# quadcopter.net
KiCad netlist of a schematic drawn in EAGLE
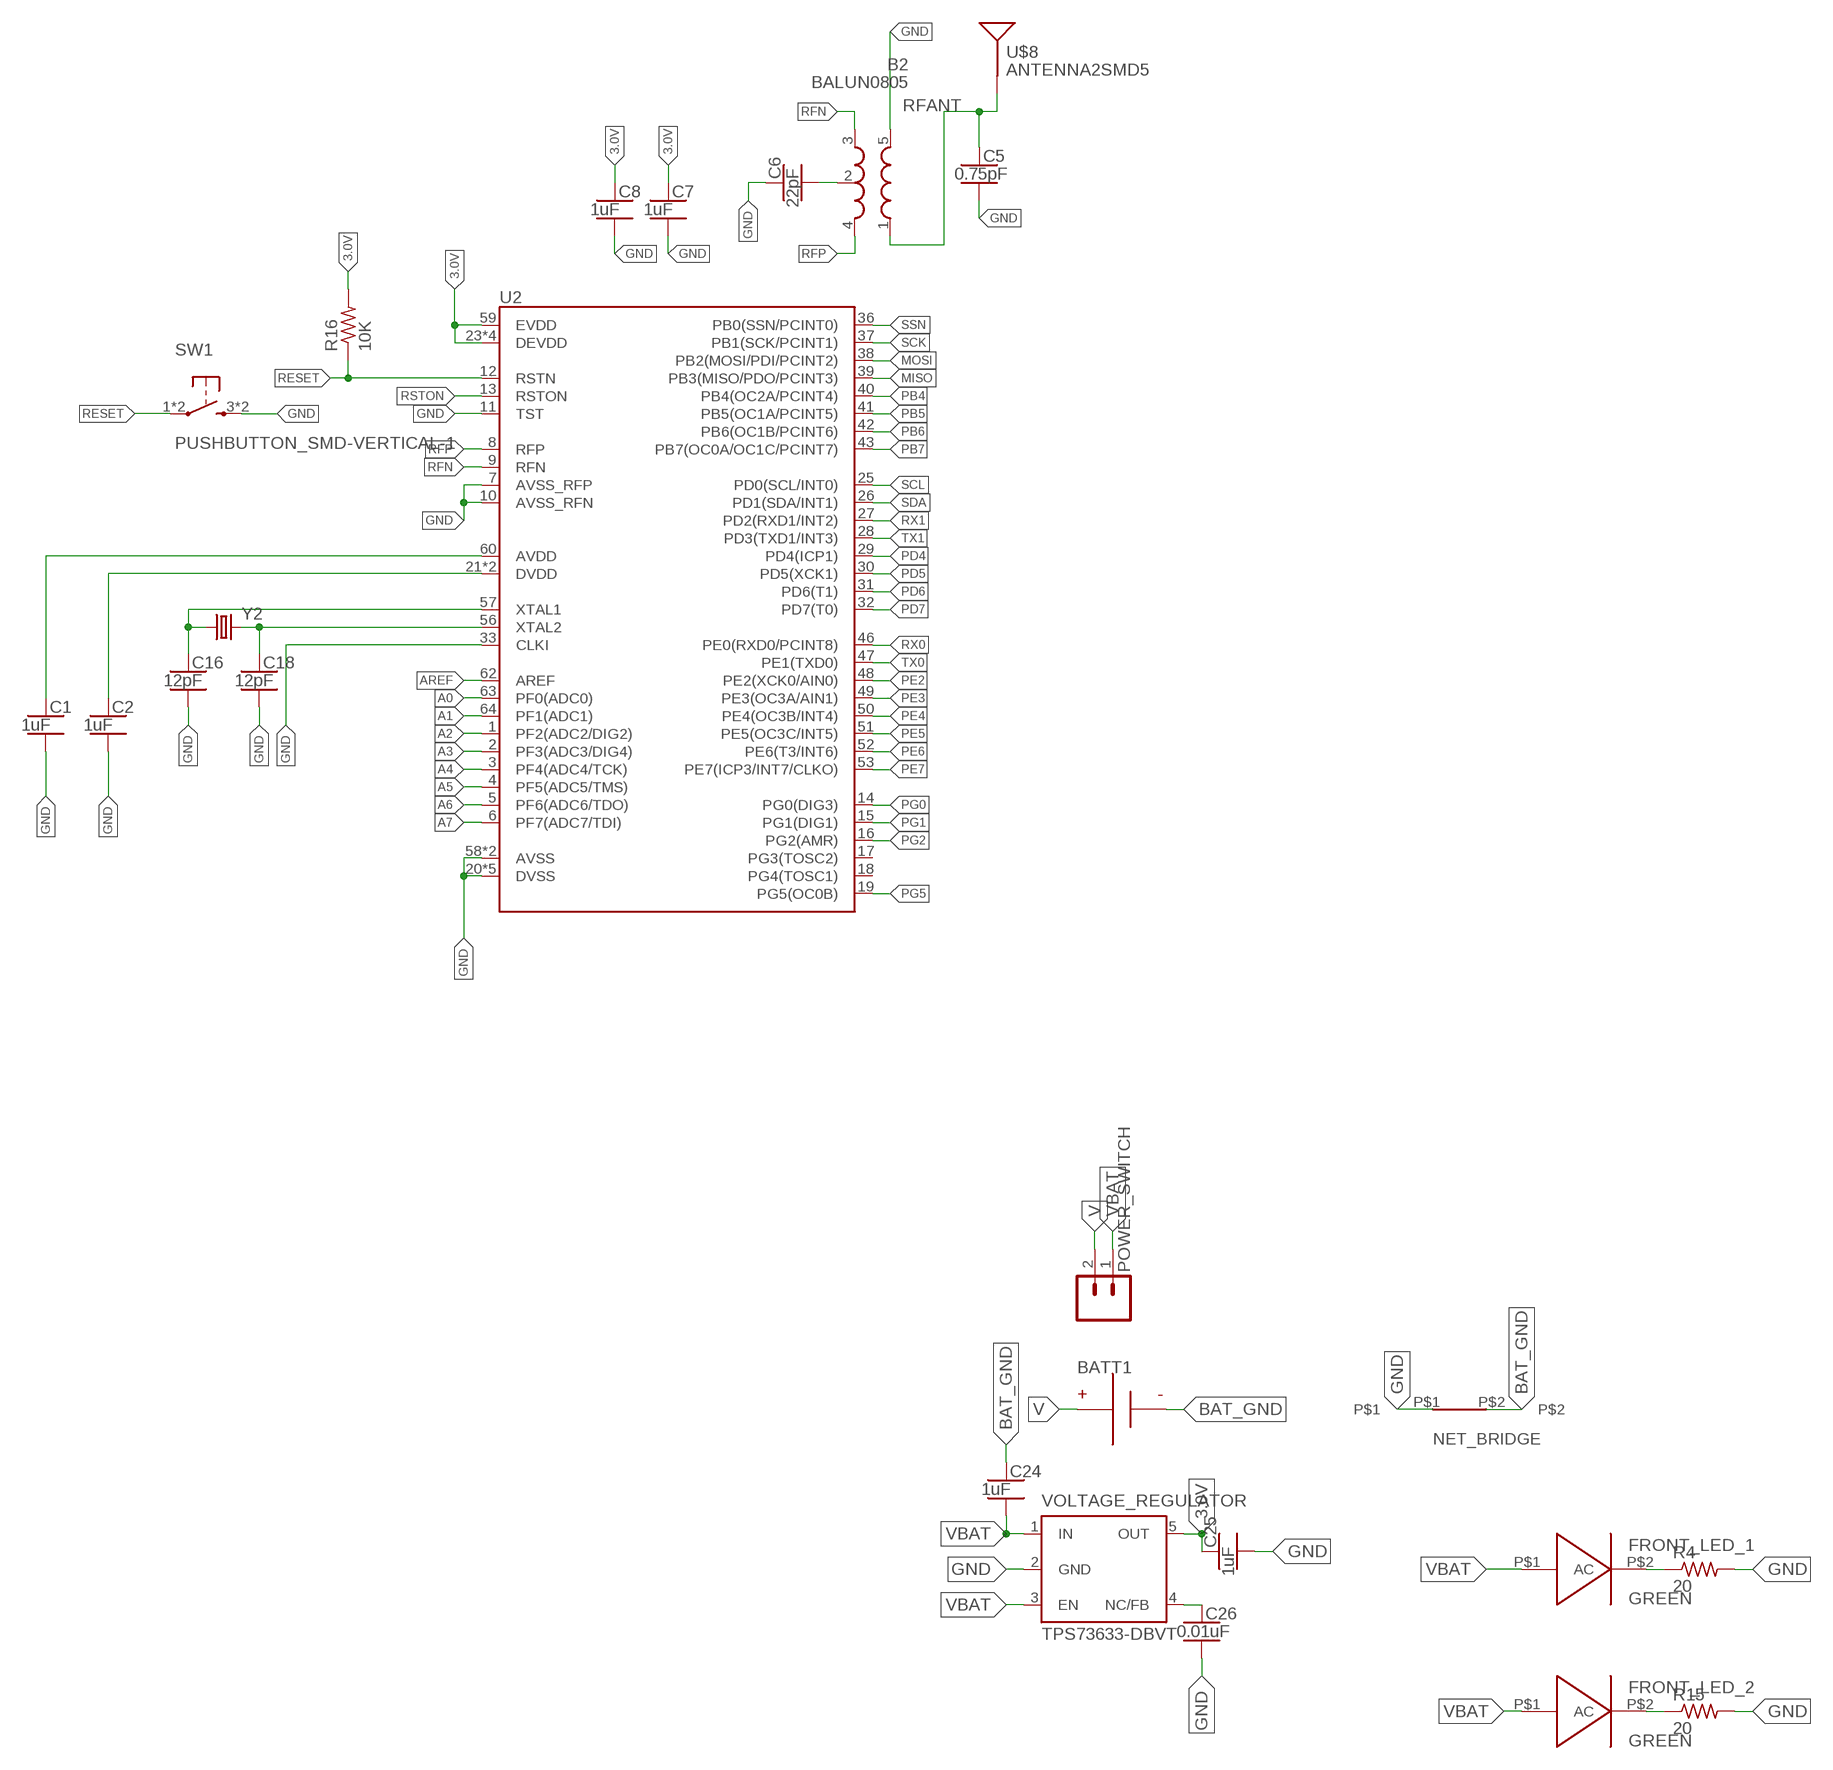
[diagram p0: schematic, sheet 1, part 1 of 2]
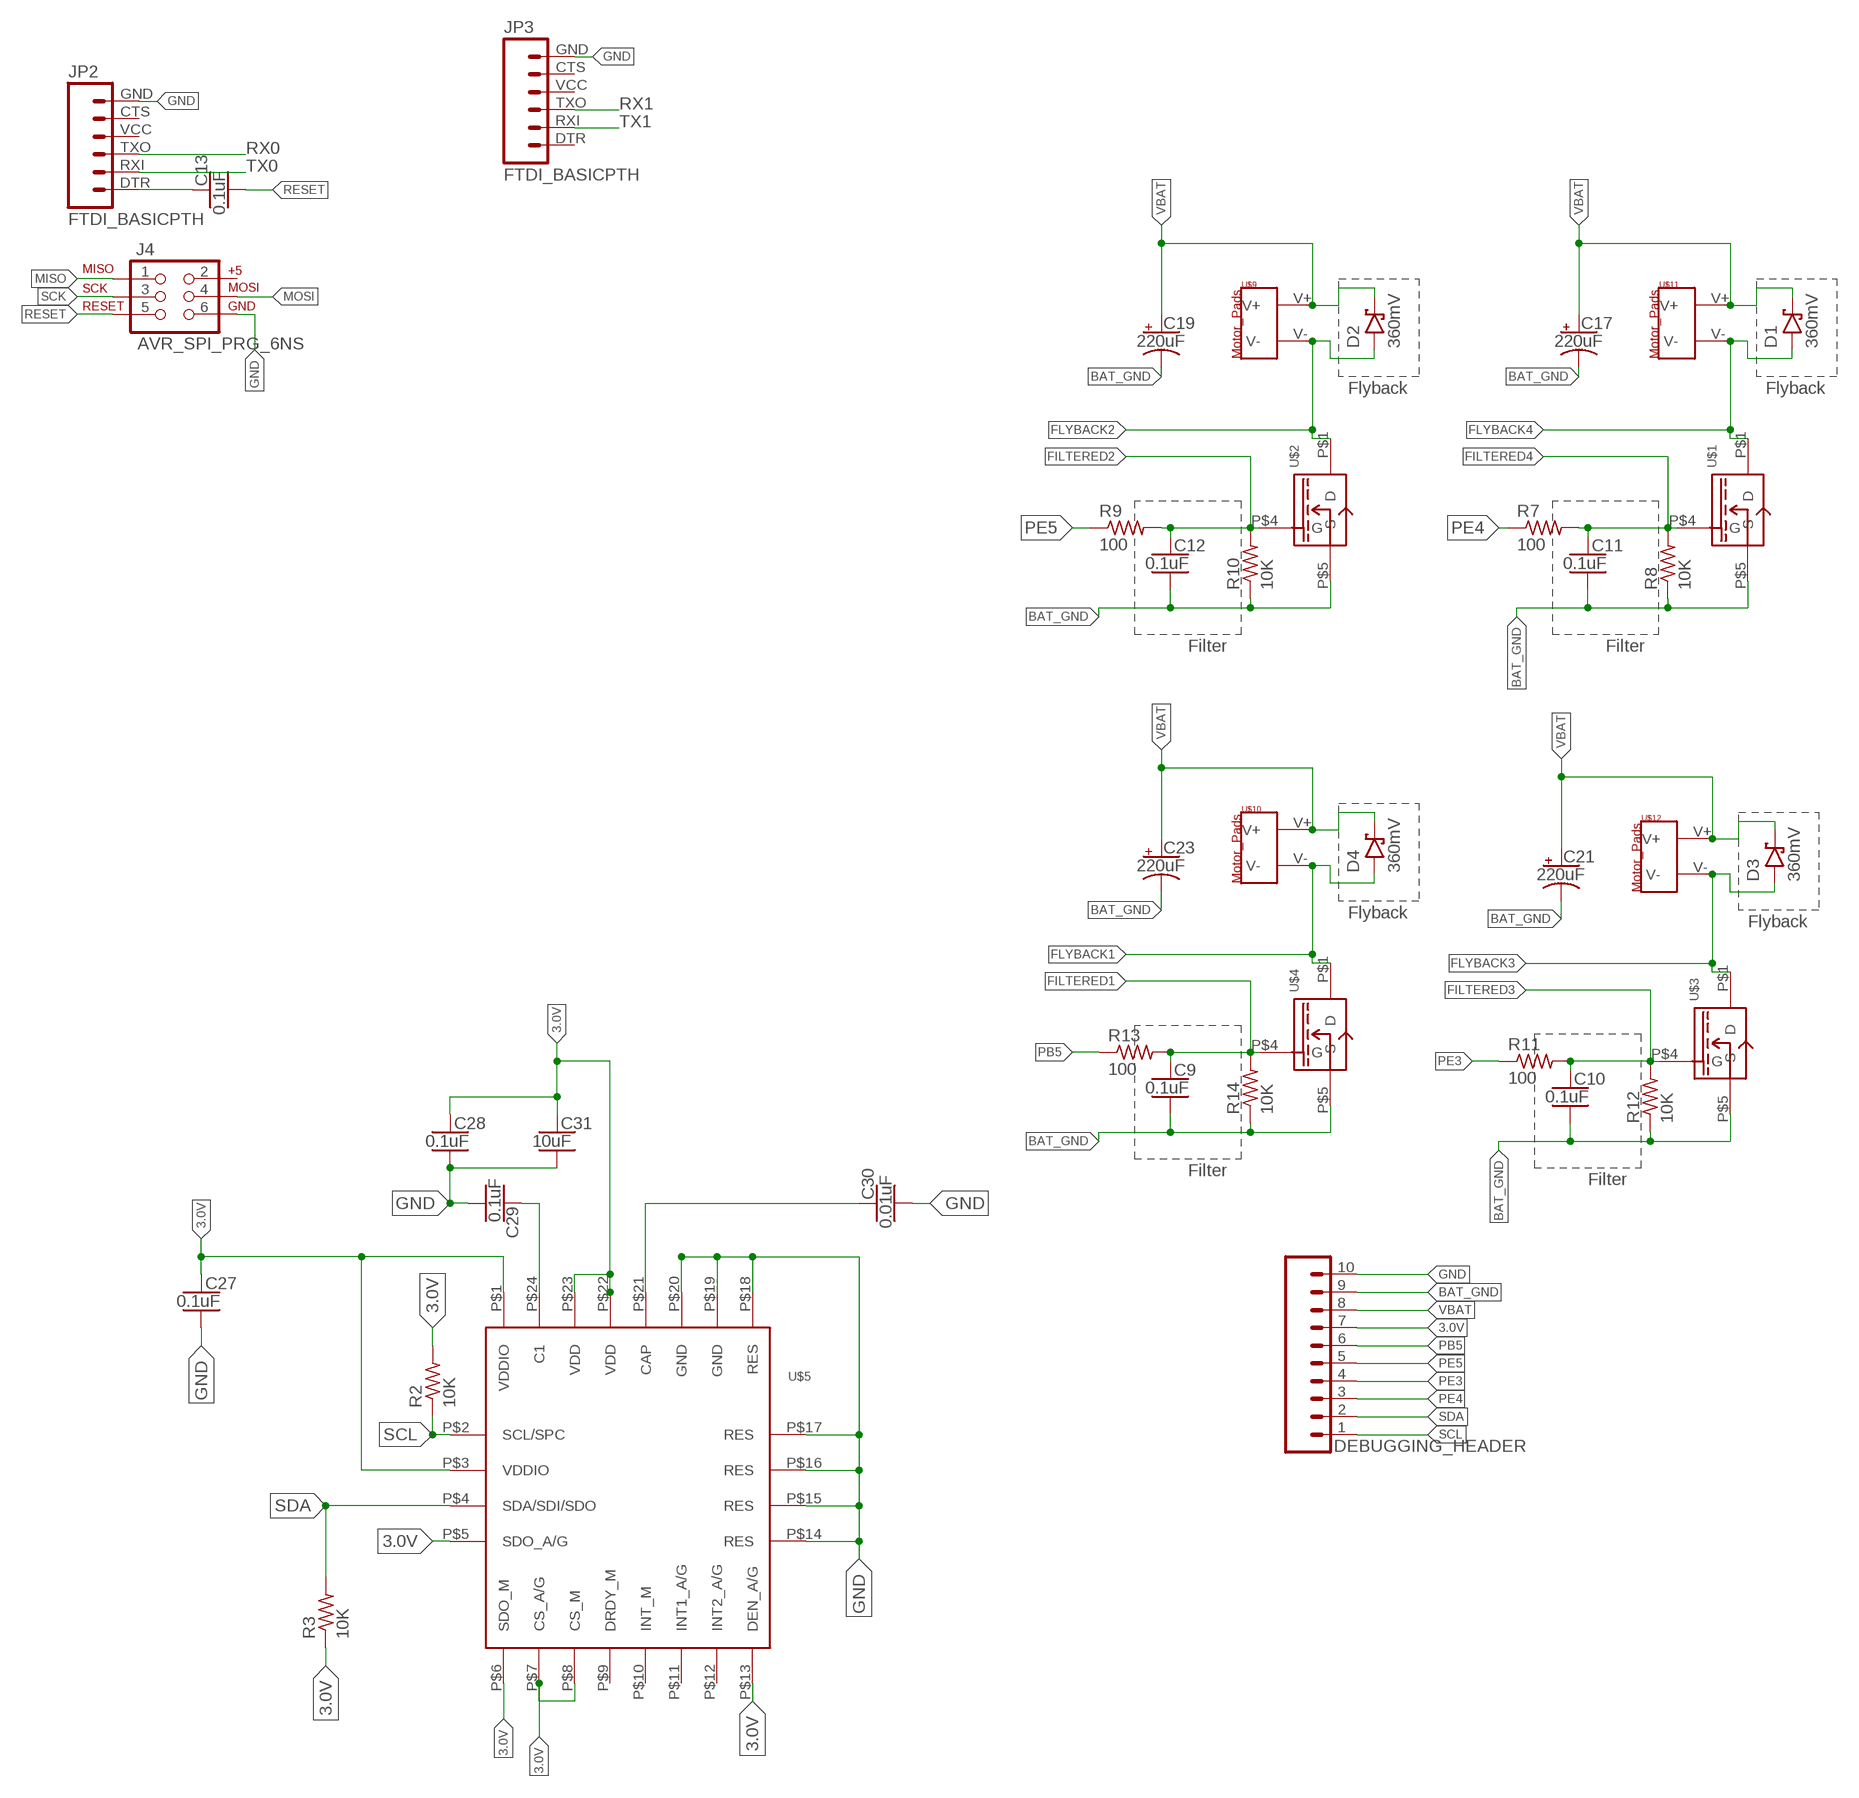
[diagram p1: schematic, sheet 1, part 2 of 2]

(export (version "E")
  (design (tool "Eeschema 10.0.6"))
  (components
    (comp (ref "B2")
      (value "BALUN0805")
      (footprint "eagle-import:BALUN")
      (fields (field (name "MFR") "Wurth Electronics Inc") (field (name "MPN") "748421245"))
      (libsource (lib "eagle-import") (part "BALUN0805"))
    )
    (comp (ref "BATT1")
      (value "BATTERY-HUBSAN-W/HOLDER")
      (footprint "eagle-import:BATTERY-W_HOLDER-380MAH-HUBSAN")
      (fields
        (field (name "MFR") "HUBSAN")
        (field (name "MPN") "X4-H107C-8-in-1")
        (field (name "CREATOR") "Swanson")
      )
      (libsource (lib "eagle-import") (part "BATTERY-HUBSAN-W/HOLDER"))
    )
    (comp (ref "C1")
      (value "1uF")
      (footprint "eagle-import:CAPC2012X140_HS")
      (fields
        (field (name "MFR") "Murata Electronics North America")
        (field (name "MPN") "GRM21BR71H105KA12L")
      )
      (libsource (lib "eagle-import") (part "CAPACITOR-NP_SMD-2012-0805_CERAMIC-1UF"))
    )
    (comp (ref "C2")
      (value "1uF")
      (footprint "eagle-import:CAPC2012X140_HS")
      (fields
        (field (name "MFR") "Murata Electronics North America")
        (field (name "MPN") "GRM21BR71H105KA12L")
      )
      (libsource (lib "eagle-import") (part "CAPACITOR-NP_SMD-2012-0805_CERAMIC-1UF"))
    )
    (comp (ref "C5")
      (value "0.75pF")
      (footprint "eagle-import:CAPC2012X140_HS")
      (fields
        (field (name "MFR") "Murata Electronics North America")
        (field (name "MPN") "GQM2195C2AR75CB01D")
      )
      (libsource (lib "eagle-import") (part "CAPACITOR-NP_SMD-2012-0805_CERAMIC-0.75PF"))
    )
    (comp (ref "C6")
      (value "22pF")
      (footprint "eagle-import:CAPC2012X140_HS")
      (fields
        (field (name "MFR") "Murata Electronics North America")
        (field (name "MPN") "GRM21A5C2E220JW01D")
      )
      (libsource (lib "eagle-import") (part "CAPACITOR-NP_SMD-2012-0805_CERAMIC-22PF"))
    )
    (comp (ref "C7")
      (value "1uF")
      (footprint "eagle-import:CAPC2012X140_HS")
      (fields
        (field (name "MFR") "Murata Electronics North America")
        (field (name "MPN") "GRM21BR71H105KA12L")
      )
      (libsource (lib "eagle-import") (part "CAPACITOR-NP_SMD-2012-0805_CERAMIC-1UF"))
    )
    (comp (ref "C8")
      (value "1uF")
      (footprint "eagle-import:CAPC2012X140_HS")
      (fields
        (field (name "MFR") "Murata Electronics North America")
        (field (name "MPN") "GRM21BR71H105KA12L")
      )
      (libsource (lib "eagle-import") (part "CAPACITOR-NP_SMD-2012-0805_CERAMIC-1UF"))
    )
    (comp (ref "C9")
      (value "0.1uF")
      (footprint "eagle-import:CAPC2012X140_HS")
      (fields
        (field (name "MFR") "Murata Electronics North America")
        (field (name "MPN") "GRM21BR71H104KA01L")
      )
      (libsource (lib "eagle-import") (part "CAPACITOR-NP_SMD-2012-0805_CERAMIC-0.1UF"))
    )
    (comp (ref "C10")
      (value "0.1uF")
      (footprint "eagle-import:CAPC2012X140_HS")
      (fields
        (field (name "MFR") "Murata Electronics North America")
        (field (name "MPN") "GRM21BR71H104KA01L")
      )
      (libsource (lib "eagle-import") (part "CAPACITOR-NP_SMD-2012-0805_CERAMIC-0.1UF"))
    )
    (comp (ref "C11")
      (value "0.1uF")
      (footprint "eagle-import:CAPC2012X140_HS")
      (fields
        (field (name "MFR") "Murata Electronics North America")
        (field (name "MPN") "GRM21BR71H104KA01L")
      )
      (libsource (lib "eagle-import") (part "CAPACITOR-NP_SMD-2012-0805_CERAMIC-0.1UF"))
    )
    (comp (ref "C12")
      (value "0.1uF")
      (footprint "eagle-import:CAPC2012X140_HS")
      (fields
        (field (name "MFR") "Murata Electronics North America")
        (field (name "MPN") "GRM21BR71H104KA01L")
      )
      (libsource (lib "eagle-import") (part "CAPACITOR-NP_SMD-2012-0805_CERAMIC-0.1UF"))
    )
    (comp (ref "C13")
      (value "0.1uF")
      (footprint "eagle-import:CAPC2012X140_HS")
      (fields
        (field (name "MFR") "Murata Electronics North America")
        (field (name "MPN") "GRM21BR71H104KA01L")
      )
      (libsource (lib "eagle-import") (part "CAPACITOR-NP_SMD-2012-0805_CERAMIC-0.1UF"))
    )
    (comp (ref "C16")
      (value "12pF")
      (footprint "eagle-import:CAPC2012X140_HS")
      (fields
        (field (name "MFR") "Murata Electronics North America")
        (field (name "MPN") "GRM21A5C2E120JW01D")
      )
      (libsource (lib "eagle-import") (part "CAPACITOR-NP_SMD-2012-0805_CERAMIC-12PF"))
    )
    (comp (ref "C17")
      (value "220uF")
      (footprint "eagle-import:CAPMP7343X310_HS")
      (fields (field (name "MFR") "AVX Corporation") (field (name "MPN") "TAJD227K006RNJ"))
      (libsource (lib "eagle-import") (part "CAPACITOR-POL_SMD-7043-D_TANTALUM-220UF"))
    )
    (comp (ref "C18")
      (value "12pF")
      (footprint "eagle-import:CAPC2012X140_HS")
      (fields
        (field (name "MFR") "Murata Electronics North America")
        (field (name "MPN") "GRM21A5C2E120JW01D")
      )
      (libsource (lib "eagle-import") (part "CAPACITOR-NP_SMD-2012-0805_CERAMIC-12PF"))
    )
    (comp (ref "C19")
      (value "220uF")
      (footprint "eagle-import:CAPMP7343X310_HS")
      (fields (field (name "MFR") "AVX Corporation") (field (name "MPN") "TAJD227K006RNJ"))
      (libsource (lib "eagle-import") (part "CAPACITOR-POL_SMD-7043-D_TANTALUM-220UF"))
    )
    (comp (ref "C21")
      (value "220uF")
      (footprint "eagle-import:CAPMP7343X310_HS")
      (fields (field (name "MFR") "AVX Corporation") (field (name "MPN") "TAJD227K006RNJ"))
      (libsource (lib "eagle-import") (part "CAPACITOR-POL_SMD-7043-D_TANTALUM-220UF"))
    )
    (comp (ref "C23")
      (value "220uF")
      (footprint "eagle-import:CAPMP7343X310_HS")
      (fields (field (name "MFR") "AVX Corporation") (field (name "MPN") "TAJD227K006RNJ"))
      (libsource (lib "eagle-import") (part "CAPACITOR-POL_SMD-7043-D_TANTALUM-220UF"))
    )
    (comp (ref "C24")
      (value "1uF")
      (footprint "eagle-import:CAPC2012X140_HS")
      (fields
        (field (name "MFR") "Murata Electronics North America")
        (field (name "MPN") "GRM21BR71H105KA12L")
      )
      (libsource (lib "eagle-import") (part "CAPACITOR-NP_SMD-2012-0805_CERAMIC-1UF"))
    )
    (comp (ref "C25")
      (value "1uF")
      (footprint "eagle-import:CAPC2012X140_HS")
      (fields
        (field (name "MFR") "Murata Electronics North America")
        (field (name "MPN") "GRM21BR71H105KA12L")
      )
      (libsource (lib "eagle-import") (part "CAPACITOR-NP_SMD-2012-0805_CERAMIC-1UF"))
    )
    (comp (ref "C26")
      (value "0.01uF")
      (footprint "eagle-import:CAPC2012X140_HS")
      (fields
        (field (name "MFR") "Murata Electronics North America")
        (field (name "MPN") "GRM2195C1H103FA01D")
      )
      (libsource (lib "eagle-import") (part "CAPACITOR-NP_SMD-2012-0805_CERAMIC-0.01UF"))
    )
    (comp (ref "C27")
      (value "0.1uF")
      (footprint "eagle-import:CAPC2012X140_HS")
      (fields
        (field (name "MFR") "Murata Electronics North America")
        (field (name "MPN") "GRM21BR71H104KA01L")
      )
      (libsource (lib "eagle-import") (part "CAPACITOR-NP_SMD-2012-0805_CERAMIC-0.1UF"))
    )
    (comp (ref "C28")
      (value "0.1uF")
      (footprint "eagle-import:CAPC2012X140_HS")
      (fields
        (field (name "MFR") "Murata Electronics North America")
        (field (name "MPN") "GRM21BR71H104KA01L")
      )
      (libsource (lib "eagle-import") (part "CAPACITOR-NP_SMD-2012-0805_CERAMIC-0.1UF"))
    )
    (comp (ref "C29")
      (value "0.1uF")
      (footprint "eagle-import:CAPC2012X140_HS")
      (fields
        (field (name "MFR") "Murata Electronics North America")
        (field (name "MPN") "GRM21BR71H104KA01L")
      )
      (libsource (lib "eagle-import") (part "CAPACITOR-NP_SMD-2012-0805_CERAMIC-0.1UF"))
    )
    (comp (ref "C30")
      (value "0.01uF")
      (footprint "eagle-import:CAPC2012X140_HS")
      (fields
        (field (name "MFR") "Murata Electronics North America")
        (field (name "MPN") "GRM2195C1H103FA01D")
      )
      (libsource (lib "eagle-import") (part "CAPACITOR-NP_SMD-2012-0805_CERAMIC-0.01UF"))
    )
    (comp (ref "C31")
      (value "10uF")
      (footprint "eagle-import:CAPC2012X140_HS")
      (fields
        (field (name "MFR") "Murata Electronics North America")
        (field (name "MPN") "GRM21BR61E106KA73L")
      )
      (libsource (lib "eagle-import") (part "CAPACITOR-NP_SMD-2012-0805_CERAMIC-10UF"))
    )
    (comp (ref "D1")
      (value "360mV")
      (footprint "eagle-import:SOD3716X135_HS")
      (fields
        (field (name "MFR") "Toshiba Semiconductor and Storage")
        (field (name "MPN") "CRS08(TE85L,Q,M)")
      )
      (libsource (lib "eagle-import") (part "DIODE-SCHOTTKY_SMD-SOD123-360MV"))
    )
    (comp (ref "D2")
      (value "360mV")
      (footprint "eagle-import:SOD3716X135_HS")
      (fields
        (field (name "MFR") "Toshiba Semiconductor and Storage")
        (field (name "MPN") "CRS08(TE85L,Q,M)")
      )
      (libsource (lib "eagle-import") (part "DIODE-SCHOTTKY_SMD-SOD123-360MV"))
    )
    (comp (ref "D3")
      (value "360mV")
      (footprint "eagle-import:SOD3716X135_HS")
      (fields
        (field (name "MFR") "Toshiba Semiconductor and Storage")
        (field (name "MPN") "CRS08(TE85L,Q,M)")
      )
      (libsource (lib "eagle-import") (part "DIODE-SCHOTTKY_SMD-SOD123-360MV"))
    )
    (comp (ref "D4")
      (value "360mV")
      (footprint "eagle-import:SOD3716X135_HS")
      (fields
        (field (name "MFR") "Toshiba Semiconductor and Storage")
        (field (name "MPN") "CRS08(TE85L,Q,M)")
      )
      (libsource (lib "eagle-import") (part "DIODE-SCHOTTKY_SMD-SOD123-360MV"))
    )
    (comp (ref "DEBUGGING_HEADER")
      (value "SIP-10_TH-254X10-1")
      (footprint "eagle-import:HDRV10W63P254_10X1_2540X254H838_HS")
      (fields (field (name "MFR") "Amphenol FCI") (field (name "MPN") "68000-110HLF"))
      (libsource (lib "eagle-import") (part "SIP-10_TH-254X10-1"))
    )
    (comp (ref "FRONT_LED_1")
      (value "GREEN")
      (footprint "eagle-import:KINGBRIGHT_LED")
      (fields
        (field (name "MFR") "Kingbright")
        (field (name "MPN") "APT2012ZGCK")
        (field (name "CREATOR") "Chris Miranda")
        (field (name "REVIEWER") "Group3")
      )
      (libsource (lib "eagle-import") (part "LED-0805-GREEN"))
    )
    (comp (ref "FRONT_LED_2")
      (value "GREEN")
      (footprint "eagle-import:KINGBRIGHT_LED")
      (fields
        (field (name "MFR") "Kingbright")
        (field (name "MPN") "APT2012ZGCK")
        (field (name "CREATOR") "Chris Miranda")
        (field (name "REVIEWER") "Group3")
      )
      (libsource (lib "eagle-import") (part "LED-0805-GREEN"))
    )
    (comp (ref "J4")
      (value "AVR_SPI_PRG_6NS")
      (footprint "eagle-import:2X3-NS")
      (fields (field (name "MFR") "Amphenol FCI") (field (name "MPN") "67997-206HLF"))
      (libsource (lib "eagle-import") (part "AVR_SPI_PRG_6NS"))
    )
    (comp (ref "JP2")
      (value "FTDI_BASICPTH")
      (footprint "eagle-import:FTDI_BASIC")
      (fields (field (name "MFR") "Amphenol FCI") (field (name "MPN") "68016-406HLF"))
      (libsource (lib "eagle-import") (part "FTDI_BASICPTH"))
    )
    (comp (ref "JP3")
      (value "FTDI_BASICPTH")
      (footprint "eagle-import:FTDI_BASIC")
      (fields (field (name "MFR") "Amphenol FCI") (field (name "MPN") "68016-406HLF"))
      (libsource (lib "eagle-import") (part "FTDI_BASICPTH"))
    )
    (comp (ref "NET_BRIDGE")
      (value "NET_BRIDGE")
      (footprint "eagle-import:NET_BRIDGE")
      (fields
        (field (name "MFR") "none")
        (field (name "CREATOR") "Chris Miranda")
        (field (name "REVIEWER") "Group3")
      )
      (libsource (lib "eagle-import") (part "NET_BRIDGE"))
    )
    (comp (ref "POWER_SWITCH")
      (value "MALE_HEADER_2POS-2X1-0.1IN")
      (footprint "eagle-import:MALE_HEADER_2X1_0.1IN")
      (fields
        (field (name "MFR") "3M")
        (field (name "MPN") "961102-6404-AR")
        (field (name "CREATOR") "SWANSON")
        (field (name "REVIEWER") "Group3")
      )
      (libsource (lib "eagle-import") (part "MALE_HEADER_2POS-2X1-0.1IN"))
    )
    (comp (ref "R2")
      (value "10K")
      (footprint "eagle-import:RESC2012X60_HS")
      (fields (field (name "MFR") "Yageo") (field (name "MPN") "RC0805JR-0710KL"))
      (libsource (lib "eagle-import") (part "RESISTOR_SMD-2012-0805-10K"))
    )
    (comp (ref "R3")
      (value "10K")
      (footprint "eagle-import:RESC2012X60_HS")
      (fields (field (name "MFR") "Yageo") (field (name "MPN") "RC0805JR-0710KL"))
      (libsource (lib "eagle-import") (part "RESISTOR_SMD-2012-0805-10K"))
    )
    (comp (ref "R4")
      (value "20")
      (footprint "eagle-import:RESC2012X60_HS")
      (fields
        (field (name "MFR") "Yageo")
        (field (name "MPN") "RC0805JR-0720RL")
        (field (name "CREATOR") "Chris Miranda")
      )
      (libsource (lib "eagle-import") (part "RESISTOR_SMD-2012-0805-20"))
    )
    (comp (ref "R7")
      (value "100")
      (footprint "eagle-import:RESC2012X60_HS")
      (fields (field (name "MFR") "Yageo") (field (name "MPN") "RC0805JR-07100RL"))
      (libsource (lib "eagle-import") (part "RESISTOR_SMD-2012-0805-100"))
    )
    (comp (ref "R8")
      (value "10K")
      (footprint "eagle-import:RESC2012X60_HS")
      (fields (field (name "MFR") "Yageo") (field (name "MPN") "RC0805JR-0710KL"))
      (libsource (lib "eagle-import") (part "RESISTOR_SMD-2012-0805-10K"))
    )
    (comp (ref "R9")
      (value "100")
      (footprint "eagle-import:RESC2012X60_HS")
      (fields (field (name "MFR") "Yageo") (field (name "MPN") "RC0805JR-07100RL"))
      (libsource (lib "eagle-import") (part "RESISTOR_SMD-2012-0805-100"))
    )
    (comp (ref "R10")
      (value "10K")
      (footprint "eagle-import:RESC2012X60_HS")
      (fields (field (name "MFR") "Yageo") (field (name "MPN") "RC0805JR-0710KL"))
      (libsource (lib "eagle-import") (part "RESISTOR_SMD-2012-0805-10K"))
    )
    (comp (ref "R11")
      (value "100")
      (footprint "eagle-import:RESC2012X60_HS")
      (fields (field (name "MFR") "Yageo") (field (name "MPN") "RC0805JR-07100RL"))
      (libsource (lib "eagle-import") (part "RESISTOR_SMD-2012-0805-100"))
    )
    (comp (ref "R12")
      (value "10K")
      (footprint "eagle-import:RESC2012X60_HS")
      (fields (field (name "MFR") "Yageo") (field (name "MPN") "RC0805JR-0710KL"))
      (libsource (lib "eagle-import") (part "RESISTOR_SMD-2012-0805-10K"))
    )
    (comp (ref "R13")
      (value "100")
      (footprint "eagle-import:RESC2012X60_HS")
      (fields (field (name "MFR") "Yageo") (field (name "MPN") "RC0805JR-07100RL"))
      (libsource (lib "eagle-import") (part "RESISTOR_SMD-2012-0805-100"))
    )
    (comp (ref "R14")
      (value "10K")
      (footprint "eagle-import:RESC2012X60_HS")
      (fields (field (name "MFR") "Yageo") (field (name "MPN") "RC0805JR-0710KL"))
      (libsource (lib "eagle-import") (part "RESISTOR_SMD-2012-0805-10K"))
    )
    (comp (ref "R15")
      (value "20")
      (footprint "eagle-import:RESC2012X60_HS")
      (fields
        (field (name "MFR") "Yageo")
        (field (name "MPN") "RC0805JR-0720RL")
        (field (name "CREATOR") "Chris Miranda")
      )
      (libsource (lib "eagle-import") (part "RESISTOR_SMD-2012-0805-20"))
    )
    (comp (ref "R16")
      (value "10K")
      (footprint "eagle-import:RESC2012X60_HS")
      (fields (field (name "MFR") "Yageo") (field (name "MPN") "RC0805JR-0710KL"))
      (libsource (lib "eagle-import") (part "RESISTOR_SMD-2012-0805-10K"))
    )
    (comp (ref "SW1")
      (value "PUSHBUTTON_SMD-VERTICAL-1")
      (footprint "eagle-import:TE_FSM8JSMA_HS")
      (fields (field (name "MFR") "TE Connectivity Alcoswitch Switches") (field (name "MPN") "FSM4JSMA"))
      (libsource (lib "eagle-import") (part "PUSHBUTTON_SMD-VERTICAL-1"))
    )
    (comp (ref "U$1")
      (value "MOFSET_SI2302CDS-T1-E3CT-ND")
      (footprint "eagle-import:MOFSET_SI2302CDS-T1-E3CT-ND")
      (fields
        (field (name "MFR") "Vishay Siliconix")
        (field (name "MPN") "SI2302CDS-T1-E3")
        (field (name "CREATOR") "Jay Ives")
        (field (name "REVIEWER") "Group3")
      )
      (libsource (lib "eagle-import") (part "MOFSET_SI2302CDS-T1-E3CT-ND"))
    )
    (comp (ref "U$2")
      (value "MOFSET_SI2302CDS-T1-E3CT-ND")
      (footprint "eagle-import:MOFSET_SI2302CDS-T1-E3CT-ND")
      (fields
        (field (name "MFR") "Vishay Siliconix")
        (field (name "MPN") "SI2302CDS-T1-E3")
        (field (name "CREATOR") "Jay Ives")
        (field (name "REVIEWER") "Group3")
      )
      (libsource (lib "eagle-import") (part "MOFSET_SI2302CDS-T1-E3CT-ND"))
    )
    (comp (ref "U$3")
      (value "MOFSET_SI2302CDS-T1-E3CT-ND")
      (footprint "eagle-import:MOFSET_SI2302CDS-T1-E3CT-ND")
      (fields
        (field (name "MFR") "Vishay Siliconix")
        (field (name "MPN") "SI2302CDS-T1-E3")
        (field (name "CREATOR") "Jay Ives")
        (field (name "REVIEWER") "Group3")
      )
      (libsource (lib "eagle-import") (part "MOFSET_SI2302CDS-T1-E3CT-ND"))
    )
    (comp (ref "U$4")
      (value "MOFSET_SI2302CDS-T1-E3CT-ND")
      (footprint "eagle-import:MOFSET_SI2302CDS-T1-E3CT-ND")
      (fields
        (field (name "MFR") "Vishay Siliconix")
        (field (name "MPN") "SI2302CDS-T1-E3")
        (field (name "CREATOR") "Jay Ives")
        (field (name "REVIEWER") "Group3")
      )
      (libsource (lib "eagle-import") (part "MOFSET_SI2302CDS-T1-E3CT-ND"))
    )
    (comp (ref "U$5")
      (value "IMU_497-14946-1-ND")
      (footprint "eagle-import:IMU_497-14946-1-ND")
      (fields
        (field (name "MFR") "STMicroelectronics")
        (field (name "MPN") "LSM9DS1TR")
        (field (name "CREATOR") "Jay Ives")
        (field (name "REVIEWER") "Group3")
      )
      (libsource (lib "eagle-import") (part "IMU_497-14946-1-ND"))
    )
    (comp (ref "U$8")
      (value "ANTENNA2SMD5")
      (footprint "eagle-import:ANTENNA-CHIP5")
      (fields (field (name "MFR") "Linx Technologies Inc.") (field (name "MPN") "ANT-2.45-CHP-T"))
      (libsource (lib "eagle-import") (part "ANTENNA2SMD5"))
    )
    (comp (ref "U$9")
      (value "MOTOR_PADS")
      (footprint "eagle-import:MOTOR_PADS")
      (fields (field (name "MFR") "NA"))
      (libsource (lib "eagle-import") (part "MOTOR_PADS"))
    )
    (comp (ref "U$10")
      (value "MOTOR_PADS")
      (footprint "eagle-import:MOTOR_PADS")
      (fields (field (name "MFR") "NA"))
      (libsource (lib "eagle-import") (part "MOTOR_PADS"))
    )
    (comp (ref "U$11")
      (value "MOTOR_PADS")
      (footprint "eagle-import:MOTOR_PADS")
      (fields (field (name "MFR") "NA"))
      (libsource (lib "eagle-import") (part "MOTOR_PADS"))
    )
    (comp (ref "U$12")
      (value "MOTOR_PADS")
      (footprint "eagle-import:MOTOR_PADS")
      (fields (field (name "MFR") "NA"))
      (libsource (lib "eagle-import") (part "MOTOR_PADS"))
    )
    (comp (ref "U2")
      (value "ATMEGA128RFA1")
      (footprint "eagle-import:QFN-64")
      (fields
        (field (name "MFR") "Atmel")
        (field (name "MPN") "ATMEGA128RFA1-ZUR00")
        (field (name "CREATOR") "Swanson")
      )
      (libsource (lib "eagle-import") (part "ATMEGA128RFA1"))
    )
    (comp (ref "VOLTAGE_REGULATOR")
      (value "TPS73633-DBVT")
      (footprint "eagle-import:SOT23-DBV")
      (fields (field (name "MFR") "Texas Instruments") (field (name "MPN") "LP3985IM5X-3.0/NOPB"))
      (libsource (lib "eagle-import") (part "TPS73633-DBVT"))
    )
    (comp (ref "Y2")
      (value "CRYSTAL5X3")
      (footprint "eagle-import:CRYSTAL-SMD-5X3")
      (fields (field (name "MFR") "Abracon LLC") (field (name "MPN") "ABM3B-16.000MHZ-B2-T"))
      (libsource (lib "eagle-import") (part "CRYSTAL5X3"))
    )
  )
  (nets
    (net (code "1") (name "/RFANT") (class "Default")
      (node (ref "B2") (pin "1") (pinfunction "IN_1") (pintype "bidirectional"))
      (node (ref "C5") (pin "1") (pinfunction "1_1") (pintype "passive"))
      (node (ref "U$8") (pin "FEED") (pinfunction "SIGNAL_FEED") (pintype "bidirectional"))
    )
    (net (code "2") (name "3.0V") (class "Default")
      (node (ref "C25") (pin "1") (pinfunction "1_1") (pintype "passive"))
      (node (ref "C27") (pin "1") (pinfunction "1_1") (pintype "passive"))
      (node (ref "C28") (pin "1") (pinfunction "1_1") (pintype "passive"))
      (node (ref "C31") (pin "1") (pinfunction "1_1") (pintype "passive"))
      (node (ref "C7") (pin "1") (pinfunction "1_1") (pintype "passive"))
      (node (ref "C8") (pin "1") (pinfunction "1_1") (pintype "passive"))
      (node (ref "DEBUGGING_HEADER") (pin "7") (pinfunction "7_7") (pintype "passive"))
      (node (ref "R16") (pin "2") (pinfunction "2_2") (pintype "passive"))
      (node (ref "R2") (pin "2") (pinfunction "2_2") (pintype "passive"))
      (node (ref "R3") (pin "1") (pinfunction "1_1") (pintype "passive"))
      (node (ref "U$5") (pin "P$1") (pinfunction "VDDIO_P$1") (pintype "bidirectional"))
      (node (ref "U$5") (pin "P$13") (pinfunction "DEN_A/G_P$13") (pintype "bidirectional"))
      (node (ref "U$5") (pin "P$22") (pinfunction "VDD_P$22") (pintype "bidirectional"))
      (node (ref "U$5") (pin "P$23") (pinfunction "VDD_P$23") (pintype "bidirectional"))
      (node (ref "U$5") (pin "P$3") (pinfunction "VDDIO_P$3") (pintype "bidirectional"))
      (node (ref "U$5") (pin "P$5") (pinfunction "SDO_A/G_P$5") (pintype "bidirectional"))
      (node (ref "U$5") (pin "P$6") (pinfunction "SDO_M_P$6") (pintype "bidirectional"))
      (node (ref "U$5") (pin "P$7") (pinfunction "CS_A/G_P$7") (pintype "bidirectional"))
      (node (ref "U$5") (pin "P$8") (pinfunction "CS_M_P$8") (pintype "bidirectional"))
      (node (ref "U2") (pin "23") (pinfunction "DEVDD_23") (pintype "bidirectional"))
      (node (ref "U2") (pin "34") (pinfunction "DEVDD_34") (pintype "bidirectional"))
      (node (ref "U2") (pin "44") (pinfunction "DEVDD_44") (pintype "bidirectional"))
      (node (ref "U2") (pin "54") (pinfunction "DEVDD_54") (pintype "bidirectional"))
      (node (ref "U2") (pin "59") (pinfunction "EVDD_59") (pintype "bidirectional"))
      (node (ref "VOLTAGE_REGULATOR") (pin "5") (pinfunction "OUT_5") (pintype "passive"))
    )
    (net (code "3") (name "A0") (class "Default")
      (node (ref "U2") (pin "63") (pinfunction "PF0(ADC0)_63") (pintype "bidirectional"))
    )
    (net (code "4") (name "A1") (class "Default")
      (node (ref "U2") (pin "64") (pinfunction "PF1(ADC1)_64") (pintype "bidirectional"))
    )
    (net (code "5") (name "A2") (class "Default")
      (node (ref "U2") (pin "1") (pinfunction "PF2(ADC2/DIG2)_1") (pintype "bidirectional"))
    )
    (net (code "6") (name "A3") (class "Default")
      (node (ref "U2") (pin "2") (pinfunction "PF3(ADC3/DIG4)_2") (pintype "bidirectional"))
    )
    (net (code "7") (name "A4") (class "Default")
      (node (ref "U2") (pin "3") (pinfunction "PF4(ADC4/TCK)_3") (pintype "bidirectional"))
    )
    (net (code "8") (name "A5") (class "Default")
      (node (ref "U2") (pin "4") (pinfunction "PF5(ADC5/TMS)_4") (pintype "bidirectional"))
    )
    (net (code "9") (name "A6") (class "Default")
      (node (ref "U2") (pin "5") (pinfunction "PF6(ADC6/TDO)_5") (pintype "bidirectional"))
    )
    (net (code "10") (name "A7") (class "Default")
      (node (ref "U2") (pin "6") (pinfunction "PF7(ADC7/TDI)_6") (pintype "bidirectional"))
    )
    (net (code "11") (name "AREF") (class "Default")
      (node (ref "U2") (pin "62") (pinfunction "AREF_62") (pintype "bidirectional"))
    )
    (net (code "12") (name "BAT_GND") (class "Default")
      (node (ref "BATT1") (pin "-") (pinfunction "N_-") (pintype "bidirectional"))
      (node (ref "C10") (pin "2") (pinfunction "2_2") (pintype "passive"))
      (node (ref "C11") (pin "2") (pinfunction "2_2") (pintype "passive"))
      (node (ref "C12") (pin "2") (pinfunction "2_2") (pintype "passive"))
      (node (ref "C17") (pin "2") (pinfunction "-_2") (pintype "passive"))
      (node (ref "C19") (pin "2") (pinfunction "-_2") (pintype "passive"))
      (node (ref "C21") (pin "2") (pinfunction "-_2") (pintype "passive"))
      (node (ref "C23") (pin "2") (pinfunction "-_2") (pintype "passive"))
      (node (ref "C24") (pin "1") (pinfunction "1_1") (pintype "passive"))
      (node (ref "C9") (pin "2") (pinfunction "2_2") (pintype "passive"))
      (node (ref "DEBUGGING_HEADER") (pin "9") (pinfunction "9_9") (pintype "passive"))
      (node (ref "NET_BRIDGE") (pin "P$2") (pinfunction "P$2_P$2") (pintype "bidirectional"))
      (node (ref "R10") (pin "1") (pinfunction "1_1") (pintype "passive"))
      (node (ref "R12") (pin "1") (pinfunction "1_1") (pintype "passive"))
      (node (ref "R14") (pin "1") (pinfunction "1_1") (pintype "passive"))
      (node (ref "R8") (pin "1") (pinfunction "1_1") (pintype "passive"))
      (node (ref "U$1") (pin "P$5") (pinfunction "S_P$5") (pintype "bidirectional"))
      (node (ref "U$2") (pin "P$5") (pinfunction "S_P$5") (pintype "bidirectional"))
      (node (ref "U$3") (pin "P$5") (pinfunction "S_P$5") (pintype "bidirectional"))
      (node (ref "U$4") (pin "P$5") (pinfunction "S_P$5") (pintype "bidirectional"))
    )
    (net (code "13") (name "FILTERED1") (class "Default")
      (node (ref "C9") (pin "1") (pinfunction "1_1") (pintype "passive"))
      (node (ref "R13") (pin "2") (pinfunction "2_2") (pintype "passive"))
      (node (ref "R14") (pin "2") (pinfunction "2_2") (pintype "passive"))
      (node (ref "U$4") (pin "P$4") (pinfunction "G_P$4") (pintype "bidirectional"))
    )
    (net (code "14") (name "FILTERED2") (class "Default")
      (node (ref "C12") (pin "1") (pinfunction "1_1") (pintype "passive"))
      (node (ref "R10") (pin "2") (pinfunction "2_2") (pintype "passive"))
      (node (ref "R9") (pin "2") (pinfunction "2_2") (pintype "passive"))
      (node (ref "U$2") (pin "P$4") (pinfunction "G_P$4") (pintype "bidirectional"))
    )
    (net (code "15") (name "FILTERED3") (class "Default")
      (node (ref "C10") (pin "1") (pinfunction "1_1") (pintype "passive"))
      (node (ref "R11") (pin "2") (pinfunction "2_2") (pintype "passive"))
      (node (ref "R12") (pin "2") (pinfunction "2_2") (pintype "passive"))
      (node (ref "U$3") (pin "P$4") (pinfunction "G_P$4") (pintype "bidirectional"))
    )
    (net (code "16") (name "FILTERED4") (class "Default")
      (node (ref "C11") (pin "1") (pinfunction "1_1") (pintype "passive"))
      (node (ref "R7") (pin "2") (pinfunction "2_2") (pintype "passive"))
      (node (ref "R8") (pin "2") (pinfunction "2_2") (pintype "passive"))
      (node (ref "U$1") (pin "P$4") (pinfunction "G_P$4") (pintype "bidirectional"))
    )
    (net (code "17") (name "FLYBACK1") (class "Default")
      (node (ref "D4") (pin "A") (pinfunction "A_A") (pintype "passive"))
      (node (ref "U$10") (pin "V-") (pinfunction "V-_V-") (pintype "bidirectional"))
      (node (ref "U$4") (pin "P$1") (pinfunction "D_P$1") (pintype "bidirectional"))
    )
    (net (code "18") (name "FLYBACK2") (class "Default")
      (node (ref "D2") (pin "A") (pinfunction "A_A") (pintype "passive"))
      (node (ref "U$2") (pin "P$1") (pinfunction "D_P$1") (pintype "bidirectional"))
      (node (ref "U$9") (pin "V-") (pinfunction "V-_V-") (pintype "bidirectional"))
    )
    (net (code "19") (name "FLYBACK3") (class "Default")
      (node (ref "D3") (pin "A") (pinfunction "A_A") (pintype "passive"))
      (node (ref "U$12") (pin "V-") (pinfunction "V-_V-") (pintype "bidirectional"))
      (node (ref "U$3") (pin "P$1") (pinfunction "D_P$1") (pintype "bidirectional"))
    )
    (net (code "20") (name "FLYBACK4") (class "Default")
      (node (ref "D1") (pin "A") (pinfunction "A_A") (pintype "passive"))
      (node (ref "U$1") (pin "P$1") (pinfunction "D_P$1") (pintype "bidirectional"))
      (node (ref "U$11") (pin "V-") (pinfunction "V-_V-") (pintype "bidirectional"))
    )
    (net (code "21") (name "GND") (class "Default")
      (node (ref "B2") (pin "5") (pinfunction "GND_5") (pintype "bidirectional"))
      (node (ref "C1") (pin "2") (pinfunction "2_2") (pintype "passive"))
      (node (ref "C16") (pin "2") (pinfunction "2_2") (pintype "passive"))
      (node (ref "C18") (pin "2") (pinfunction "2_2") (pintype "passive"))
      (node (ref "C2") (pin "2") (pinfunction "2_2") (pintype "passive"))
      (node (ref "C25") (pin "2") (pinfunction "2_2") (pintype "passive"))
      (node (ref "C26") (pin "2") (pinfunction "2_2") (pintype "passive"))
      (node (ref "C27") (pin "2") (pinfunction "2_2") (pintype "passive"))
      (node (ref "C28") (pin "2") (pinfunction "2_2") (pintype "passive"))
      (node (ref "C29") (pin "2") (pinfunction "2_2") (pintype "passive"))
      (node (ref "C30") (pin "2") (pinfunction "2_2") (pintype "passive"))
      (node (ref "C31") (pin "2") (pinfunction "2_2") (pintype "passive"))
      (node (ref "C5") (pin "2") (pinfunction "2_2") (pintype "passive"))
      (node (ref "C6") (pin "1") (pinfunction "1_1") (pintype "passive"))
      (node (ref "C7") (pin "2") (pinfunction "2_2") (pintype "passive"))
      (node (ref "C8") (pin "2") (pinfunction "2_2") (pintype "passive"))
      (node (ref "DEBUGGING_HEADER") (pin "10") (pinfunction "10_10") (pintype "passive"))
      (node (ref "J4") (pin "6") (pinfunction "6_6") (pintype "passive"))
      (node (ref "JP2") (pin "GND") (pinfunction "6_GND") (pintype "passive"))
      (node (ref "JP3") (pin "GND") (pinfunction "6_GND") (pintype "passive"))
      (node (ref "NET_BRIDGE") (pin "P$1") (pinfunction "P$1_P$1") (pintype "bidirectional"))
      (node (ref "R15") (pin "2") (pinfunction "2_2") (pintype "passive"))
      (node (ref "R4") (pin "2") (pinfunction "2_2") (pintype "passive"))
      (node (ref "SW1") (pin "3") (pinfunction "2_3") (pintype "passive"))
      (node (ref "SW1") (pin "4") (pinfunction "2_4") (pintype "passive"))
      (node (ref "U$5") (pin "P$14") (pinfunction "RES_P$14") (pintype "bidirectional"))
      (node (ref "U$5") (pin "P$15") (pinfunction "RES_P$15") (pintype "bidirectional"))
      (node (ref "U$5") (pin "P$16") (pinfunction "RES_P$16") (pintype "bidirectional"))
      (node (ref "U$5") (pin "P$17") (pinfunction "RES_P$17") (pintype "bidirectional"))
      (node (ref "U$5") (pin "P$18") (pinfunction "RES_P$18") (pintype "bidirectional"))
      (node (ref "U$5") (pin "P$19") (pinfunction "GND_P$19") (pintype "bidirectional"))
      (node (ref "U$5") (pin "P$20") (pinfunction "GND_P$20") (pintype "bidirectional"))
      (node (ref "U2") (pin "10") (pinfunction "AVSS_RFN_10") (pintype "bidirectional"))
      (node (ref "U2") (pin "11") (pinfunction "TST_11") (pintype "bidirectional"))
      (node (ref "U2") (pin "20") (pinfunction "DVSS_20") (pintype "bidirectional"))
      (node (ref "U2") (pin "24") (pinfunction "DVSS_24") (pintype "bidirectional"))
      (node (ref "U2") (pin "33") (pinfunction "CLKI_33") (pintype "bidirectional"))
      (node (ref "U2") (pin "35") (pinfunction "DVSS_35") (pintype "bidirectional"))
      (node (ref "U2") (pin "45") (pinfunction "DVSS_45") (pintype "bidirectional"))
      (node (ref "U2") (pin "55") (pinfunction "DVSS_55") (pintype "bidirectional"))
      (node (ref "U2") (pin "58") (pinfunction "AVSS_58") (pintype "bidirectional"))
      (node (ref "U2") (pin "61") (pinfunction "AVSS_61") (pintype "bidirectional"))
      (node (ref "U2") (pin "7") (pinfunction "AVSS_RFP_7") (pintype "bidirectional"))
      (node (ref "VOLTAGE_REGULATOR") (pin "2") (pinfunction "GND_2") (pintype "input"))
    )
    (net (code "22") (name "MISO") (class "Default")
      (node (ref "J4") (pin "1") (pinfunction "1_1") (pintype "passive"))
      (node (ref "U2") (pin "39") (pinfunction "PB3(MISO/PDO/PCINT3)_39") (pintype "bidirectional"))
    )
    (net (code "23") (name "MOSI") (class "Default")
      (node (ref "J4") (pin "4") (pinfunction "4_4") (pintype "passive"))
      (node (ref "U2") (pin "38") (pinfunction "PB2(MOSI/PDI/PCINT2)_38") (pintype "bidirectional"))
    )
    (net (code "24") (name "Net-(B2-GND-Pad2)") (class "Default")
      (node (ref "B2") (pin "2") (pinfunction "GND_2") (pintype "bidirectional"))
      (node (ref "C6") (pin "2") (pinfunction "2_2") (pintype "passive"))
    )
    (net (code "25") (name "Net-(C2-Pad1)") (class "Default")
      (node (ref "C2") (pin "1") (pinfunction "1_1") (pintype "passive"))
      (node (ref "U2") (pin "21") (pinfunction "DVDD_21") (pintype "bidirectional"))
      (node (ref "U2") (pin "22") (pinfunction "DVDD_22") (pintype "bidirectional"))
    )
    (net (code "26") (name "Net-(FRONT_LED_1-C)") (class "Default")
      (node (ref "FRONT_LED_1") (pin "P$2") (pinfunction "C_P$2") (pintype "bidirectional"))
      (node (ref "R4") (pin "1") (pinfunction "1_1") (pintype "passive"))
    )
    (net (code "27") (name "Net-(FRONT_LED_2-C)") (class "Default")
      (node (ref "FRONT_LED_2") (pin "P$2") (pinfunction "C_P$2") (pintype "bidirectional"))
      (node (ref "R15") (pin "1") (pinfunction "1_1") (pintype "passive"))
    )
    (net (code "28") (name "Net-(JP2-1)") (class "Default")
      (node (ref "C13") (pin "1") (pinfunction "1_1") (pintype "passive"))
      (node (ref "JP2") (pin "DTR") (pinfunction "1_DTR") (pintype "passive"))
    )
    (net (code "29") (name "Net-(U$5-C1)") (class "Default")
      (node (ref "C29") (pin "1") (pinfunction "1_1") (pintype "passive"))
      (node (ref "U$5") (pin "P$24") (pinfunction "C1_P$24") (pintype "bidirectional"))
    )
    (net (code "30") (name "Net-(U$5-CAP)") (class "Default")
      (node (ref "C30") (pin "1") (pinfunction "1_1") (pintype "passive"))
      (node (ref "U$5") (pin "P$21") (pinfunction "CAP_P$21") (pintype "bidirectional"))
    )
    (net (code "31") (name "Net-(U2-AVDD)") (class "Default")
      (node (ref "C1") (pin "1") (pinfunction "1_1") (pintype "passive"))
      (node (ref "U2") (pin "60") (pinfunction "AVDD_60") (pintype "bidirectional"))
    )
    (net (code "32") (name "Net-(U2-XTAL1)") (class "Default")
      (node (ref "C16") (pin "1") (pinfunction "1_1") (pintype "passive"))
      (node (ref "U2") (pin "57") (pinfunction "XTAL1_57") (pintype "bidirectional"))
      (node (ref "Y2") (pin "1") (pinfunction "1_1") (pintype "passive"))
    )
    (net (code "33") (name "Net-(U2-XTAL2)") (class "Default")
      (node (ref "C18") (pin "1") (pinfunction "1_1") (pintype "passive"))
      (node (ref "U2") (pin "56") (pinfunction "XTAL2_56") (pintype "bidirectional"))
      (node (ref "Y2") (pin "3") (pinfunction "2_3") (pintype "passive"))
    )
    (net (code "34") (name "Net-(VOLTAGE_REGULATOR-NC{slash}FB)") (class "Default")
      (node (ref "C26") (pin "1") (pinfunction "1_1") (pintype "passive"))
      (node (ref "VOLTAGE_REGULATOR") (pin "4") (pinfunction "NC/FB_4") (pintype "passive"))
    )
    (net (code "35") (name "PB4") (class "Default")
      (node (ref "U2") (pin "40") (pinfunction "PB4(OC2A/PCINT4)_40") (pintype "bidirectional"))
    )
    (net (code "36") (name "PB5") (class "Default")
      (node (ref "DEBUGGING_HEADER") (pin "6") (pinfunction "6_6") (pintype "passive"))
      (node (ref "R13") (pin "1") (pinfunction "1_1") (pintype "passive"))
      (node (ref "U2") (pin "41") (pinfunction "PB5(OC1A/PCINT5)_41") (pintype "bidirectional"))
    )
    (net (code "37") (name "PB6") (class "Default")
      (node (ref "U2") (pin "42") (pinfunction "PB6(OC1B/PCINT6)_42") (pintype "bidirectional"))
    )
    (net (code "38") (name "PB7") (class "Default")
      (node (ref "U2") (pin "43") (pinfunction "PB7(OC0A/OC1C/PCINT7)_43") (pintype "bidirectional"))
    )
    (net (code "39") (name "PD4") (class "Default")
      (node (ref "U2") (pin "29") (pinfunction "PD4(ICP1)_29") (pintype "bidirectional"))
    )
    (net (code "40") (name "PD5") (class "Default")
      (node (ref "U2") (pin "30") (pinfunction "PD5(XCK1)_30") (pintype "bidirectional"))
    )
    (net (code "41") (name "PD6") (class "Default")
      (node (ref "U2") (pin "31") (pinfunction "PD6(T1)_31") (pintype "bidirectional"))
    )
    (net (code "42") (name "PD7") (class "Default")
      (node (ref "U2") (pin "32") (pinfunction "PD7(T0)_32") (pintype "bidirectional"))
    )
    (net (code "43") (name "PE2") (class "Default")
      (node (ref "U2") (pin "48") (pinfunction "PE2(XCK0/AIN0)_48") (pintype "bidirectional"))
    )
    (net (code "44") (name "PE3") (class "Default")
      (node (ref "DEBUGGING_HEADER") (pin "4") (pinfunction "4_4") (pintype "passive"))
      (node (ref "R11") (pin "1") (pinfunction "1_1") (pintype "passive"))
      (node (ref "U2") (pin "49") (pinfunction "PE3(OC3A/AIN1)_49") (pintype "bidirectional"))
    )
    (net (code "45") (name "PE4") (class "Default")
      (node (ref "DEBUGGING_HEADER") (pin "3") (pinfunction "3_3") (pintype "passive"))
      (node (ref "R7") (pin "1") (pinfunction "1_1") (pintype "passive"))
      (node (ref "U2") (pin "50") (pinfunction "PE4(OC3B/INT4)_50") (pintype "bidirectional"))
    )
    (net (code "46") (name "PE5") (class "Default")
      (node (ref "DEBUGGING_HEADER") (pin "5") (pinfunction "5_5") (pintype "passive"))
      (node (ref "R9") (pin "1") (pinfunction "1_1") (pintype "passive"))
      (node (ref "U2") (pin "51") (pinfunction "PE5(OC3C/INT5)_51") (pintype "bidirectional"))
    )
    (net (code "47") (name "PE6") (class "Default")
      (node (ref "U2") (pin "52") (pinfunction "PE6(T3/INT6)_52") (pintype "bidirectional"))
    )
    (net (code "48") (name "PE7") (class "Default")
      (node (ref "U2") (pin "53") (pinfunction "PE7(ICP3/INT7/CLKO)_53") (pintype "bidirectional"))
    )
    (net (code "49") (name "PG0") (class "Default")
      (node (ref "U2") (pin "14") (pinfunction "PG0(DIG3)_14") (pintype "bidirectional"))
    )
    (net (code "50") (name "PG1") (class "Default")
      (node (ref "U2") (pin "15") (pinfunction "PG1(DIG1)_15") (pintype "bidirectional"))
    )
    (net (code "51") (name "PG2") (class "Default")
      (node (ref "U2") (pin "16") (pinfunction "PG2(AMR)_16") (pintype "bidirectional"))
    )
    (net (code "52") (name "PG5") (class "Default")
      (node (ref "U2") (pin "19") (pinfunction "PG5(OC0B)_19") (pintype "bidirectional"))
    )
    (net (code "53") (name "RESET") (class "Default")
      (node (ref "C13") (pin "2") (pinfunction "2_2") (pintype "passive"))
      (node (ref "J4") (pin "5") (pinfunction "5_5") (pintype "passive"))
      (node (ref "R16") (pin "1") (pinfunction "1_1") (pintype "passive"))
      (node (ref "SW1") (pin "1") (pinfunction "1_1") (pintype "passive"))
      (node (ref "SW1") (pin "2") (pinfunction "1_2") (pintype "passive"))
      (node (ref "U2") (pin "12") (pinfunction "RSTN_12") (pintype "bidirectional"))
    )
    (net (code "54") (name "RFN") (class "Default")
      (node (ref "B2") (pin "3") (pinfunction "OUT2_3") (pintype "bidirectional"))
      (node (ref "U2") (pin "9") (pinfunction "RFN_9") (pintype "bidirectional"))
    )
    (net (code "55") (name "RFP") (class "Default")
      (node (ref "B2") (pin "4") (pinfunction "OUT1_4") (pintype "bidirectional"))
      (node (ref "U2") (pin "8") (pinfunction "RFP_8") (pintype "bidirectional"))
    )
    (net (code "56") (name "RSTON") (class "Default")
      (node (ref "U2") (pin "13") (pinfunction "RSTON_13") (pintype "bidirectional"))
    )
    (net (code "57") (name "RX0") (class "Default")
      (node (ref "JP2") (pin "TXO") (pinfunction "3_TXO") (pintype "passive"))
      (node (ref "U2") (pin "46") (pinfunction "PE0(RXD0/PCINT8)_46") (pintype "bidirectional"))
    )
    (net (code "58") (name "RX1") (class "Default")
      (node (ref "JP3") (pin "TXO") (pinfunction "3_TXO") (pintype "passive"))
      (node (ref "U2") (pin "27") (pinfunction "PD2(RXD1/INT2)_27") (pintype "bidirectional"))
    )
    (net (code "59") (name "SCK") (class "Default")
      (node (ref "J4") (pin "3") (pinfunction "3_3") (pintype "passive"))
      (node (ref "U2") (pin "37") (pinfunction "PB1(SCK/PCINT1)_37") (pintype "bidirectional"))
    )
    (net (code "60") (name "SCL") (class "Default")
      (node (ref "DEBUGGING_HEADER") (pin "1") (pinfunction "1_1") (pintype "passive"))
      (node (ref "R2") (pin "1") (pinfunction "1_1") (pintype "passive"))
      (node (ref "U$5") (pin "P$2") (pinfunction "SCL/SPC_P$2") (pintype "bidirectional"))
      (node (ref "U2") (pin "25") (pinfunction "PD0(SCL/INT0)_25") (pintype "bidirectional"))
    )
    (net (code "61") (name "SDA") (class "Default")
      (node (ref "DEBUGGING_HEADER") (pin "2") (pinfunction "2_2") (pintype "passive"))
      (node (ref "R3") (pin "2") (pinfunction "2_2") (pintype "passive"))
      (node (ref "U$5") (pin "P$4") (pinfunction "SDA/SDI/SDO_P$4") (pintype "bidirectional"))
      (node (ref "U2") (pin "26") (pinfunction "PD1(SDA/INT1)_26") (pintype "bidirectional"))
    )
    (net (code "62") (name "SSN") (class "Default")
      (node (ref "U2") (pin "36") (pinfunction "PB0(SSN/PCINT0)_36") (pintype "bidirectional"))
    )
    (net (code "63") (name "TX0") (class "Default")
      (node (ref "JP2") (pin "RXI") (pinfunction "2_RXI") (pintype "passive"))
      (node (ref "U2") (pin "47") (pinfunction "PE1(TXD0)_47") (pintype "bidirectional"))
    )
    (net (code "64") (name "TX1") (class "Default")
      (node (ref "JP3") (pin "RXI") (pinfunction "2_RXI") (pintype "passive"))
      (node (ref "U2") (pin "28") (pinfunction "PD3(TXD1/INT3)_28") (pintype "bidirectional"))
    )
    (net (code "65") (name "V") (class "Default")
      (node (ref "BATT1") (pin "+") (pinfunction "P_+") (pintype "bidirectional"))
      (node (ref "POWER_SWITCH") (pin "2") (pinfunction "2_2") (pintype "passive"))
    )
    (net (code "66") (name "VBAT") (class "Default")
      (node (ref "C17") (pin "1") (pinfunction "+_1") (pintype "passive"))
      (node (ref "C19") (pin "1") (pinfunction "+_1") (pintype "passive"))
      (node (ref "C21") (pin "1") (pinfunction "+_1") (pintype "passive"))
      (node (ref "C23") (pin "1") (pinfunction "+_1") (pintype "passive"))
      (node (ref "C24") (pin "2") (pinfunction "2_2") (pintype "passive"))
      (node (ref "D1") (pin "C") (pinfunction "C_C") (pintype "passive"))
      (node (ref "D2") (pin "C") (pinfunction "C_C") (pintype "passive"))
      (node (ref "D3") (pin "C") (pinfunction "C_C") (pintype "passive"))
      (node (ref "D4") (pin "C") (pinfunction "C_C") (pintype "passive"))
      (node (ref "DEBUGGING_HEADER") (pin "8") (pinfunction "8_8") (pintype "passive"))
      (node (ref "FRONT_LED_1") (pin "P$1") (pinfunction "A_P$1") (pintype "bidirectional"))
      (node (ref "FRONT_LED_2") (pin "P$1") (pinfunction "A_P$1") (pintype "bidirectional"))
      (node (ref "POWER_SWITCH") (pin "1") (pinfunction "1_1") (pintype "passive"))
      (node (ref "U$10") (pin "V+") (pinfunction "V+_V+") (pintype "bidirectional"))
      (node (ref "U$11") (pin "V+") (pinfunction "V+_V+") (pintype "bidirectional"))
      (node (ref "U$12") (pin "V+") (pinfunction "V+_V+") (pintype "bidirectional"))
      (node (ref "U$9") (pin "V+") (pinfunction "V+_V+") (pintype "bidirectional"))
      (node (ref "VOLTAGE_REGULATOR") (pin "1") (pinfunction "IN_1") (pintype "input"))
      (node (ref "VOLTAGE_REGULATOR") (pin "3") (pinfunction "EN_3") (pintype "input"))
    )
    (net (code "67") (name "unconnected-(J4-Pad2)") (class "Default")
      (node (ref "J4") (pin "2") (pinfunction "2_2") (pintype "passive"))
    )
    (net (code "68") (name "unconnected-(JP2-4-PadVCC)") (class "Default")
      (node (ref "JP2") (pin "VCC") (pinfunction "4_VCC") (pintype "passive"))
    )
    (net (code "69") (name "unconnected-(JP2-5-PadCTS)") (class "Default")
      (node (ref "JP2") (pin "CTS") (pinfunction "5_CTS") (pintype "passive"))
    )
    (net (code "70") (name "unconnected-(JP3-1-PadDTR)") (class "Default")
      (node (ref "JP3") (pin "DTR") (pinfunction "1_DTR") (pintype "passive"))
    )
    (net (code "71") (name "unconnected-(JP3-4-PadVCC)") (class "Default")
      (node (ref "JP3") (pin "VCC") (pinfunction "4_VCC") (pintype "passive"))
    )
    (net (code "72") (name "unconnected-(JP3-5-PadCTS)") (class "Default")
      (node (ref "JP3") (pin "CTS") (pinfunction "5_CTS") (pintype "passive"))
    )
    (net (code "73") (name "unconnected-(U$5-DRDY_M-PadP$9)") (class "Default")
      (node (ref "U$5") (pin "P$9") (pinfunction "DRDY_M_P$9") (pintype "bidirectional"))
    )
    (net (code "74") (name "unconnected-(U$5-INT1_A{slash}G-PadP$11)") (class "Default")
      (node (ref "U$5") (pin "P$11") (pinfunction "INT1_A/G_P$11") (pintype "bidirectional"))
    )
    (net (code "75") (name "unconnected-(U$5-INT2_A{slash}G-PadP$12)") (class "Default")
      (node (ref "U$5") (pin "P$12") (pinfunction "INT2_A/G_P$12") (pintype "bidirectional"))
    )
    (net (code "76") (name "unconnected-(U$5-INT_M-PadP$10)") (class "Default")
      (node (ref "U$5") (pin "P$10") (pinfunction "INT_M_P$10") (pintype "bidirectional"))
    )
    (net (code "77") (name "unconnected-(U2-PG3(TOSC2)-Pad17)") (class "Default")
      (node (ref "U2") (pin "17") (pinfunction "PG3(TOSC2)_17") (pintype "bidirectional"))
    )
    (net (code "78") (name "unconnected-(U2-PG4(TOSC1)-Pad18)") (class "Default")
      (node (ref "U2") (pin "18") (pinfunction "PG4(TOSC1)_18") (pintype "bidirectional"))
    )
  )
)
